# IMU_Digital_Combo_Board__-_6_Degrees_of_.net
KiCad netlist of a schematic drawn in EAGLE
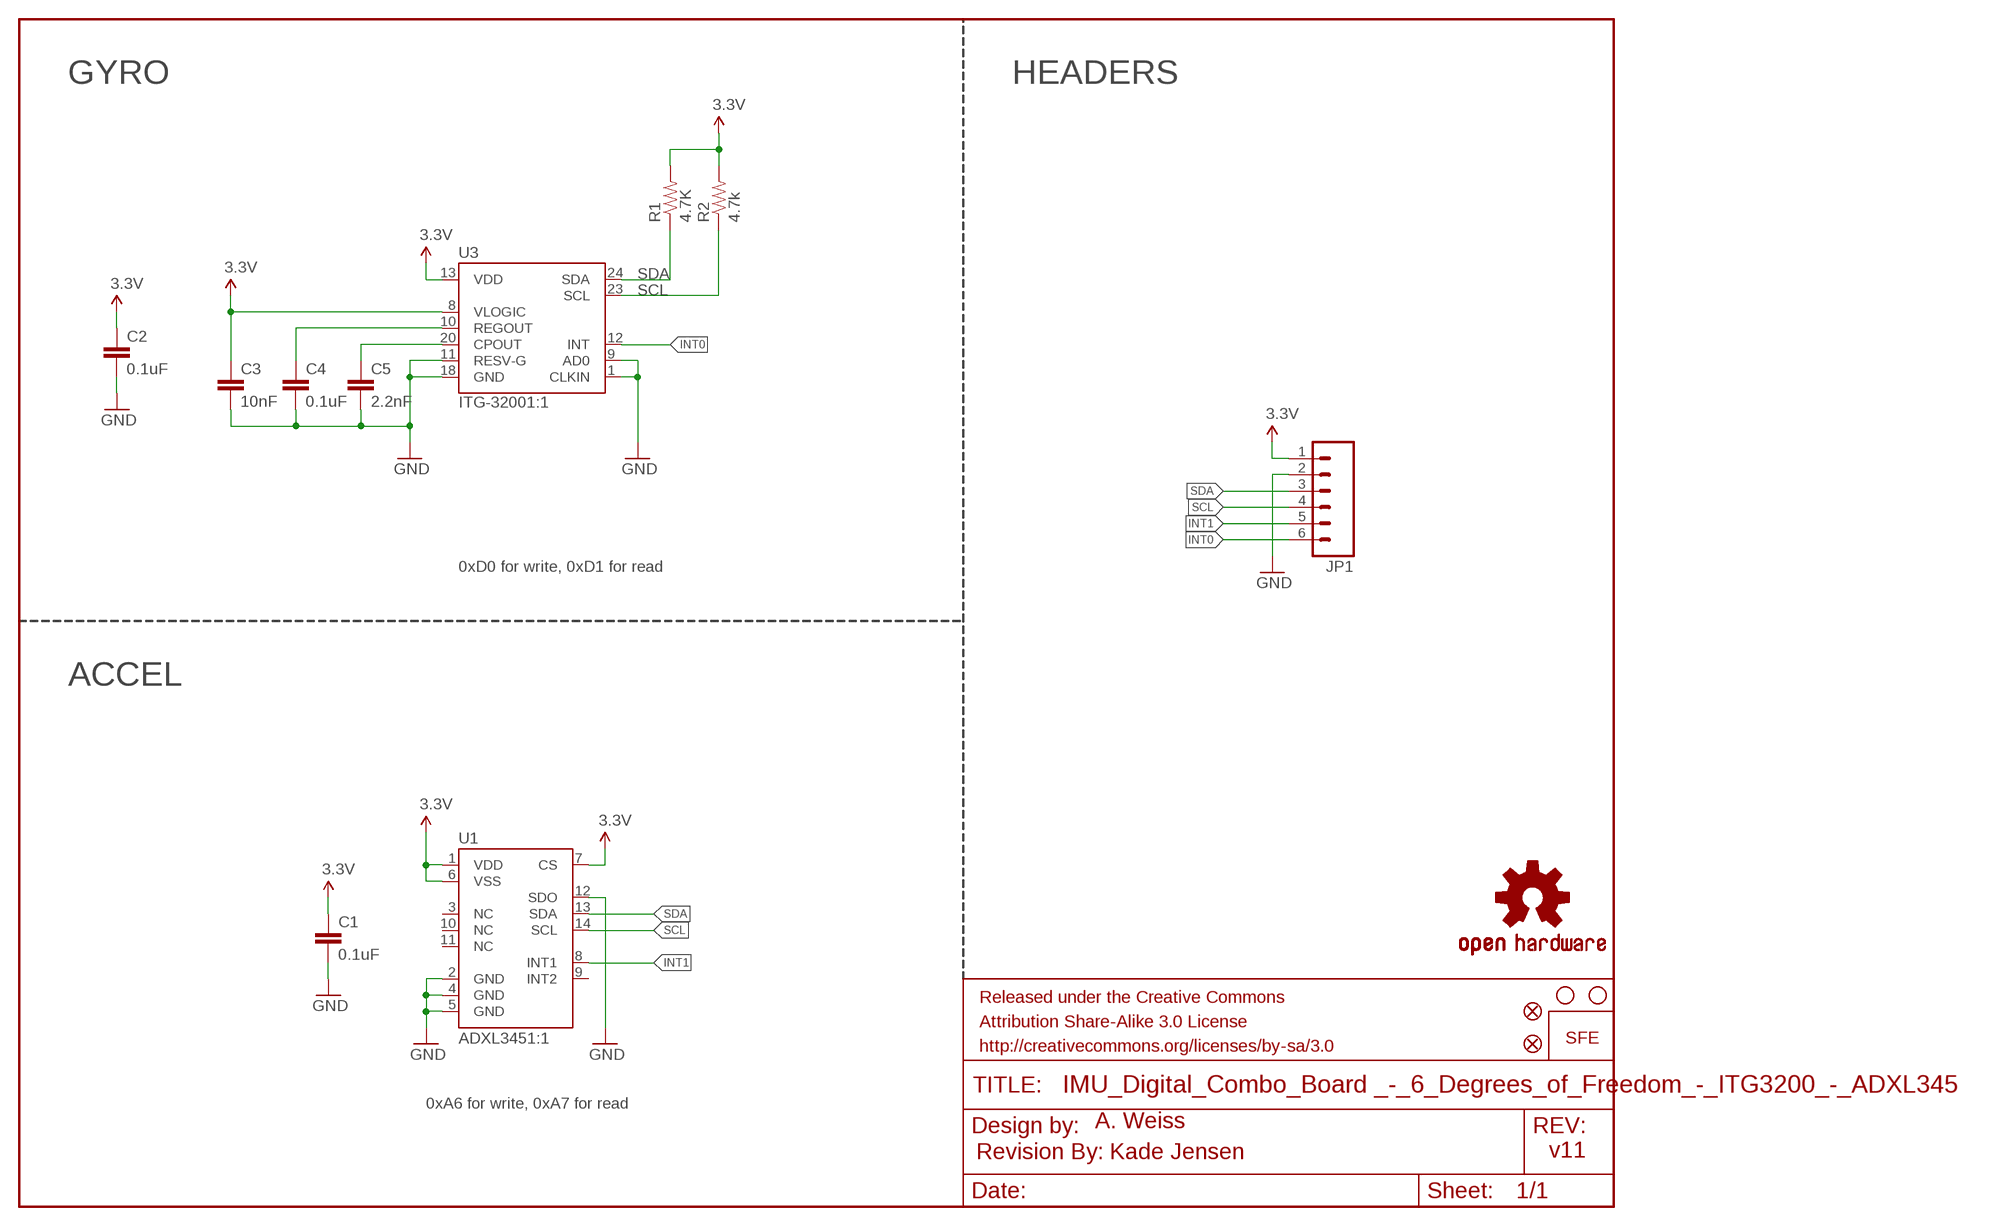
[diagram p0: schematic, sheet 1]

(export (version "E")
  (design (tool "Eeschema 10.0.6"))
  (components
    (comp (ref "C1")
      (value "0.1uF")
      (footprint "eagle-import:0603-CAP")
      (libsource (lib "eagle-import") (part "CAP0603-CAP"))
    )
    (comp (ref "C2")
      (value "0.1uF")
      (footprint "eagle-import:0603-CAP")
      (libsource (lib "eagle-import") (part "CAP0603-CAP"))
    )
    (comp (ref "C3")
      (value "10nF")
      (footprint "eagle-import:0603-CAP")
      (libsource (lib "eagle-import") (part "CAP0603-CAP"))
    )
    (comp (ref "C4")
      (value "0.1uF")
      (footprint "eagle-import:0603-CAP")
      (libsource (lib "eagle-import") (part "CAP0603-CAP"))
    )
    (comp (ref "C5")
      (value "2.2nF")
      (footprint "eagle-import:0603-CAP")
      (libsource (lib "eagle-import") (part "CAP0603-CAP"))
    )
    (comp (ref "FRAME1")
      (value "FRAME-LETTER")
      (footprint "eagle-import:CREATIVE_COMMONS")
      (libsource (lib "eagle-import") (part "FRAME-LETTER"))
    )
    (comp (ref "JP1")
      (value "M06SIP")
      (footprint "eagle-import:1X06")
      (libsource (lib "eagle-import") (part "M06SIP"))
    )
    (comp (ref "JP2")
      (value "STAND-OFF")
      (footprint "eagle-import:STAND-OFF")
      (libsource (lib "eagle-import") (part "STAND-OFF"))
    )
    (comp (ref "JP3")
      (value "LOGO-SFESK")
      (footprint "eagle-import:SFE-LOGO-FLAME")
      (libsource (lib "eagle-import") (part "LOGO-SFESK"))
    )
    (comp (ref "JP4")
      (value "FIDUCIAL1X2")
      (footprint "eagle-import:FIDUCIAL-1X2")
      (libsource (lib "eagle-import") (part "FIDUCIAL1X2"))
    )
    (comp (ref "JP5")
      (value "STAND-OFF")
      (footprint "eagle-import:STAND-OFF")
      (libsource (lib "eagle-import") (part "STAND-OFF"))
    )
    (comp (ref "JP6")
      (value "FIDUCIAL1X2")
      (footprint "eagle-import:FIDUCIAL-1X2")
      (libsource (lib "eagle-import") (part "FIDUCIAL1X2"))
    )
    (comp (ref "R1")
      (value "4.7K")
      (footprint "eagle-import:0603-RES")
      (libsource (lib "eagle-import") (part "RESISTOR0603-RES"))
    )
    (comp (ref "R2")
      (value "4.7k")
      (footprint "eagle-import:0603-RES")
      (libsource (lib "eagle-import") (part "RESISTOR0603-RES"))
    )
    (comp (ref "U$1")
      (value "REVISION")
      (footprint "eagle-import:REVISION")
      (libsource (lib "eagle-import") (part "REVISION"))
    )
    (comp (ref "U$2")
      (value "OSHW-LOGOS")
      (footprint "eagle-import:OSHW-LOGO-S")
      (libsource (lib "eagle-import") (part "OSHW-LOGOS"))
    )
    (comp (ref "U1")
      (value "ADXL3451:1")
      (footprint "eagle-import:LGA14")
      (libsource (lib "eagle-import") (part "ADXL3451{colon}1"))
    )
    (comp (ref "U3")
      (value "ITG-32001:1")
      (footprint "eagle-import:QFN-24_ITG3200_1_1")
      (libsource (lib "eagle-import") (part "ITG-32001{colon}1"))
    )
  )
  (nets
    (net (code "1") (name "3.3V") (class "Default")
      (node (ref "C1") (pin "1") (pinfunction "1_1") (pintype "passive"))
      (node (ref "C2") (pin "1") (pinfunction "1_1") (pintype "passive"))
      (node (ref "C3") (pin "1") (pinfunction "1_1") (pintype "passive"))
      (node (ref "JP1") (pin "1") (pinfunction "1_1") (pintype "passive"))
      (node (ref "R1") (pin "2") (pinfunction "2_2") (pintype "passive"))
      (node (ref "R2") (pin "2") (pinfunction "2_2") (pintype "passive"))
      (node (ref "U1") (pin "1") (pinfunction "VDD_1") (pintype "bidirectional"))
      (node (ref "U1") (pin "6") (pinfunction "VSS_6") (pintype "bidirectional"))
      (node (ref "U1") (pin "7") (pinfunction "CS_7") (pintype "bidirectional"))
      (node (ref "U3") (pin "13") (pinfunction "VDD_13") (pintype "bidirectional"))
      (node (ref "U3") (pin "8") (pinfunction "VLOGIC_8") (pintype "bidirectional"))
    )
    (net (code "2") (name "GND") (class "Default")
      (node (ref "C1") (pin "2") (pinfunction "2_2") (pintype "passive"))
      (node (ref "C2") (pin "2") (pinfunction "2_2") (pintype "passive"))
      (node (ref "C3") (pin "2") (pinfunction "2_2") (pintype "passive"))
      (node (ref "C4") (pin "2") (pinfunction "2_2") (pintype "passive"))
      (node (ref "C5") (pin "2") (pinfunction "2_2") (pintype "passive"))
      (node (ref "JP1") (pin "2") (pinfunction "2_2") (pintype "passive"))
      (node (ref "U1") (pin "12") (pinfunction "SDO_12") (pintype "bidirectional"))
      (node (ref "U1") (pin "2") (pinfunction "GND_2") (pintype "bidirectional"))
      (node (ref "U1") (pin "4") (pinfunction "GND_4") (pintype "bidirectional"))
      (node (ref "U1") (pin "5") (pinfunction "GND_5") (pintype "bidirectional"))
      (node (ref "U3") (pin "1") (pinfunction "CLKIN_1") (pintype "bidirectional"))
      (node (ref "U3") (pin "11") (pinfunction "RESV-G_11") (pintype "bidirectional"))
      (node (ref "U3") (pin "18") (pinfunction "GND_18") (pintype "bidirectional"))
      (node (ref "U3") (pin "9") (pinfunction "AD0_9") (pintype "bidirectional"))
    )
    (net (code "3") (name "INT0") (class "Default")
      (node (ref "JP1") (pin "6") (pinfunction "6_6") (pintype "passive"))
      (node (ref "U3") (pin "12") (pinfunction "INT_12") (pintype "bidirectional"))
    )
    (net (code "4") (name "INT1") (class "Default")
      (node (ref "JP1") (pin "5") (pinfunction "5_5") (pintype "passive"))
      (node (ref "U1") (pin "8") (pinfunction "INT1_8") (pintype "bidirectional"))
    )
    (net (code "5") (name "Net-(U3-CPOUT)") (class "Default")
      (node (ref "C5") (pin "1") (pinfunction "1_1") (pintype "passive"))
      (node (ref "U3") (pin "20") (pinfunction "CPOUT_20") (pintype "bidirectional"))
    )
    (net (code "6") (name "Net-(U3-REGOUT)") (class "Default")
      (node (ref "C4") (pin "1") (pinfunction "1_1") (pintype "passive"))
      (node (ref "U3") (pin "10") (pinfunction "REGOUT_10") (pintype "bidirectional"))
    )
    (net (code "7") (name "SCL") (class "Default")
      (node (ref "JP1") (pin "4") (pinfunction "4_4") (pintype "passive"))
      (node (ref "R2") (pin "1") (pinfunction "1_1") (pintype "passive"))
      (node (ref "U1") (pin "14") (pinfunction "SCL_14") (pintype "bidirectional"))
      (node (ref "U3") (pin "23") (pinfunction "SCL_23") (pintype "bidirectional"))
    )
    (net (code "8") (name "SDA") (class "Default")
      (node (ref "JP1") (pin "3") (pinfunction "3_3") (pintype "passive"))
      (node (ref "R1") (pin "1") (pinfunction "1_1") (pintype "passive"))
      (node (ref "U1") (pin "13") (pinfunction "SDA_13") (pintype "bidirectional"))
      (node (ref "U3") (pin "24") (pinfunction "SDA_24") (pintype "bidirectional"))
    )
    (net (code "9") (name "unconnected-(U1-INT2-Pad9)") (class "Default")
      (node (ref "U1") (pin "9") (pinfunction "INT2_9") (pintype "bidirectional"))
    )
    (net (code "10") (name "unconnected-(U1-NC-Pad3)") (class "Default")
      (node (ref "U1") (pin "3") (pinfunction "NC_3") (pintype "bidirectional"))
    )
    (net (code "11") (name "unconnected-(U1-NC-Pad10)") (class "Default")
      (node (ref "U1") (pin "10") (pinfunction "NC_10") (pintype "bidirectional"))
    )
    (net (code "12") (name "unconnected-(U1-NC-Pad11)") (class "Default")
      (node (ref "U1") (pin "11") (pinfunction "NC_11") (pintype "bidirectional"))
    )
  )
)
